# QuadEncoder.net
KiCad netlist of a schematic drawn in EAGLE
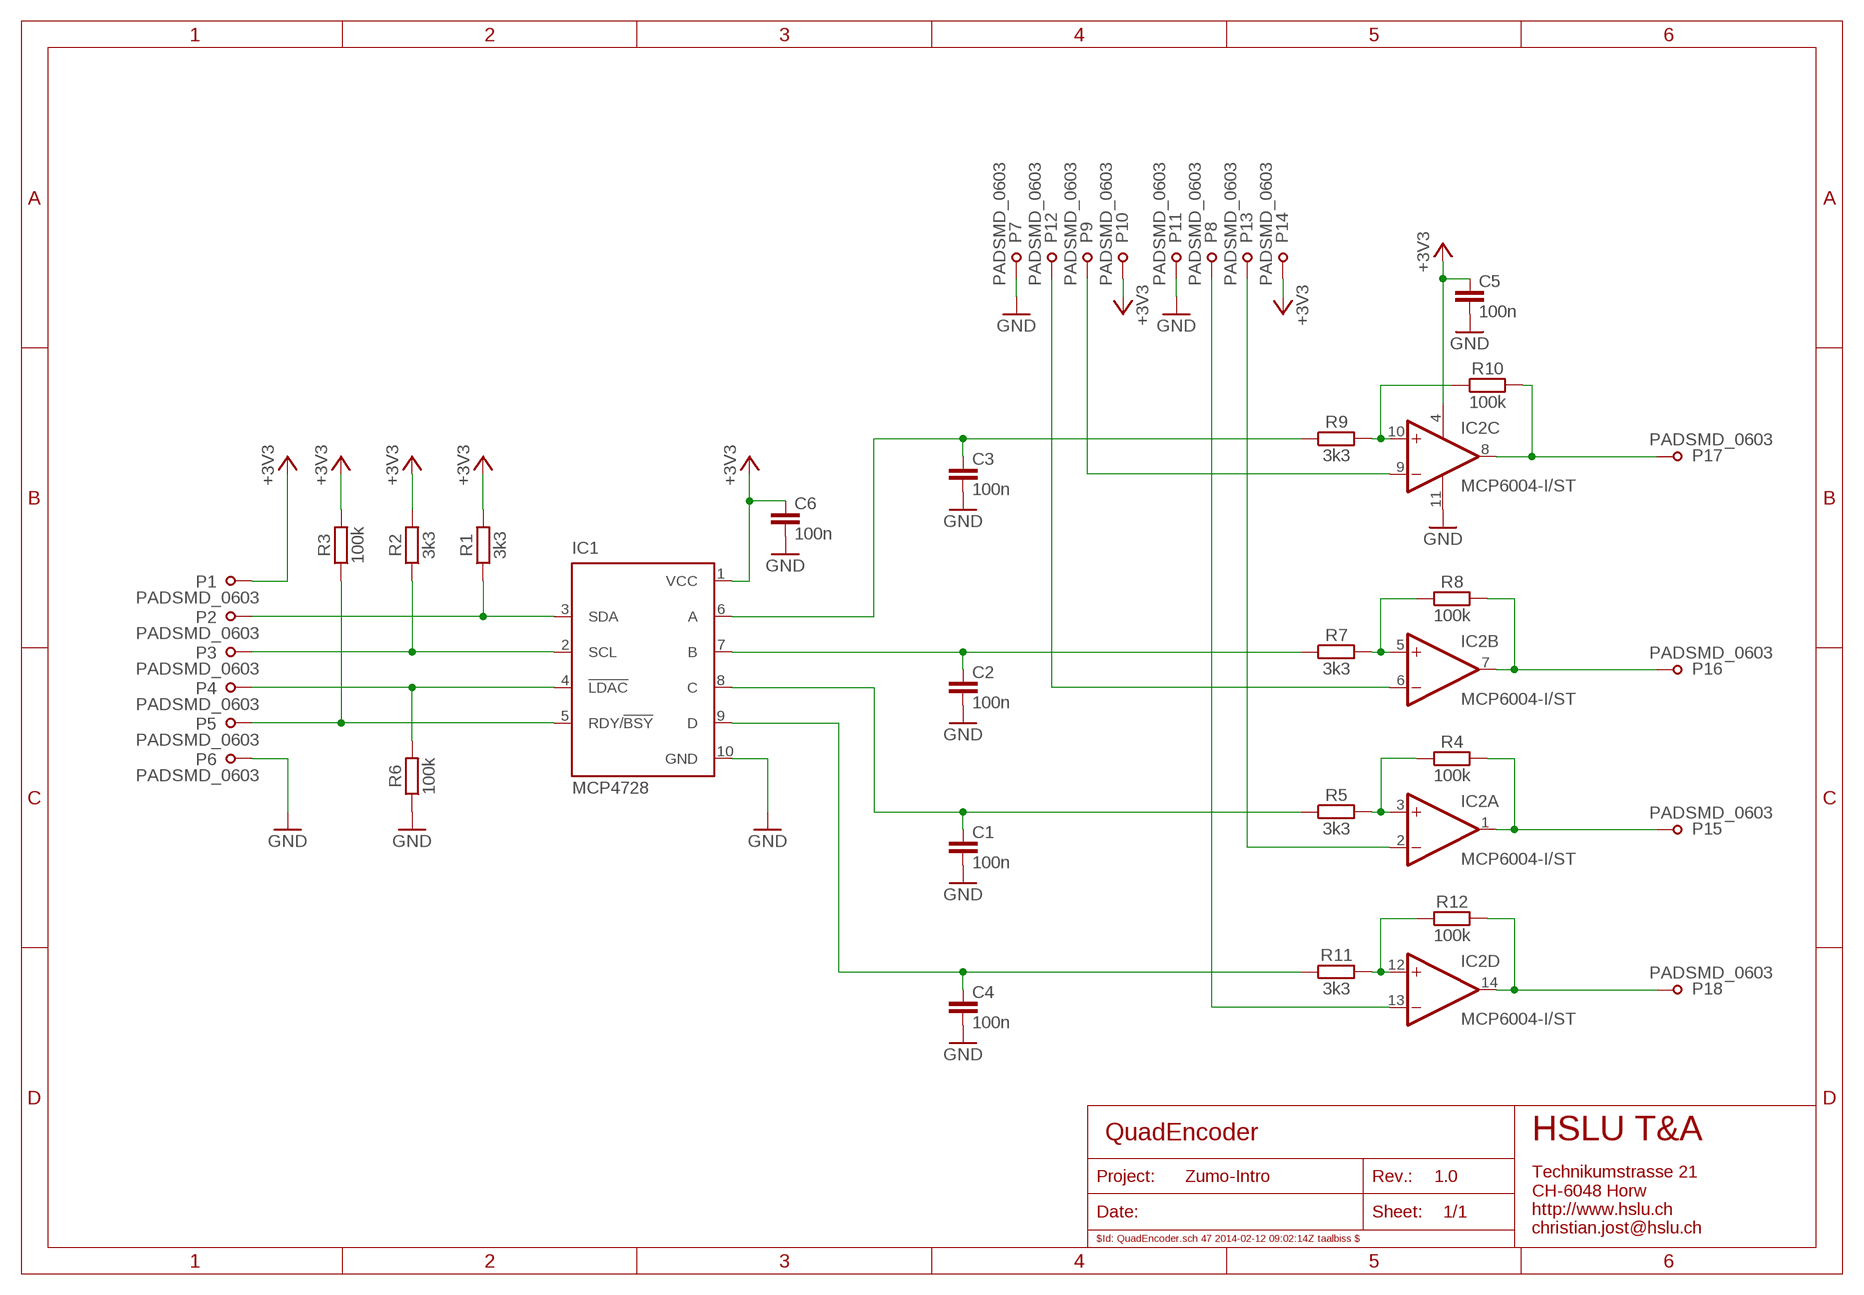
[diagram p0: schematic, sheet 1]

(export (version "E")
  (design (tool "Eeschema 10.0.6"))
  (components
    (comp (ref "C1")
      (value "100n")
      (footprint "eagle-import:C0805-R")
      (libsource (lib "eagle-import") (part "C0805"))
    )
    (comp (ref "C2")
      (value "100n")
      (footprint "eagle-import:C0805-R")
      (libsource (lib "eagle-import") (part "C0805"))
    )
    (comp (ref "C3")
      (value "100n")
      (footprint "eagle-import:C0805-R")
      (libsource (lib "eagle-import") (part "C0805"))
    )
    (comp (ref "C4")
      (value "100n")
      (footprint "eagle-import:C0805-R")
      (libsource (lib "eagle-import") (part "C0805"))
    )
    (comp (ref "C5")
      (value "100n")
      (footprint "eagle-import:C0805-R")
      (libsource (lib "eagle-import") (part "C0805"))
    )
    (comp (ref "C6")
      (value "100n")
      (footprint "eagle-import:C0805-R")
      (libsource (lib "eagle-import") (part "C0805"))
    )
    (comp (ref "IC1")
      (value "MCP4728")
      (footprint "eagle-import:MSOP10")
      (libsource (lib "eagle-import") (part "MCP4728"))
    )
    (comp (ref "IC2")
      (value "MCP6004-I/ST")
      (footprint "eagle-import:TSSOP14")
      (fields (field (name "DISTRIBUTOR") "Mouser") (field (name "DISTRIBUTOR_NR") "579-MCP6004-I/ST"))
      (libsource (lib "eagle-import") (part "MCP6004/ST-I"))
    )
    (comp (ref "P1")
      (value "PADSMD_0603")
      (footprint "eagle-import:PAD_SMD_0603")
      (libsource (lib "eagle-import") (part "PADSMD_0603"))
    )
    (comp (ref "P2")
      (value "PADSMD_0603")
      (footprint "eagle-import:PAD_SMD_0603")
      (libsource (lib "eagle-import") (part "PADSMD_0603"))
    )
    (comp (ref "P3")
      (value "PADSMD_0603")
      (footprint "eagle-import:PAD_SMD_0603")
      (libsource (lib "eagle-import") (part "PADSMD_0603"))
    )
    (comp (ref "P4")
      (value "PADSMD_0603")
      (footprint "eagle-import:PAD_SMD_0603")
      (libsource (lib "eagle-import") (part "PADSMD_0603"))
    )
    (comp (ref "P5")
      (value "PADSMD_0603")
      (footprint "eagle-import:PAD_SMD_0603")
      (libsource (lib "eagle-import") (part "PADSMD_0603"))
    )
    (comp (ref "P6")
      (value "PADSMD_0603")
      (footprint "eagle-import:PAD_SMD_0603")
      (libsource (lib "eagle-import") (part "PADSMD_0603"))
    )
    (comp (ref "P7")
      (value "PADSMD_0603")
      (footprint "eagle-import:PAD_SMD_0603")
      (libsource (lib "eagle-import") (part "PADSMD_0603"))
    )
    (comp (ref "P8")
      (value "PADSMD_0603")
      (footprint "eagle-import:PAD_SMD_0603")
      (libsource (lib "eagle-import") (part "PADSMD_0603"))
    )
    (comp (ref "P9")
      (value "PADSMD_0603")
      (footprint "eagle-import:PAD_SMD_0603")
      (libsource (lib "eagle-import") (part "PADSMD_0603"))
    )
    (comp (ref "P10")
      (value "PADSMD_0603")
      (footprint "eagle-import:PAD_SMD_0603")
      (libsource (lib "eagle-import") (part "PADSMD_0603"))
    )
    (comp (ref "P11")
      (value "PADSMD_0603")
      (footprint "eagle-import:PAD_SMD_0603")
      (libsource (lib "eagle-import") (part "PADSMD_0603"))
    )
    (comp (ref "P12")
      (value "PADSMD_0603")
      (footprint "eagle-import:PAD_SMD_0603")
      (libsource (lib "eagle-import") (part "PADSMD_0603"))
    )
    (comp (ref "P13")
      (value "PADSMD_0603")
      (footprint "eagle-import:PAD_SMD_0603")
      (libsource (lib "eagle-import") (part "PADSMD_0603"))
    )
    (comp (ref "P14")
      (value "PADSMD_0603")
      (footprint "eagle-import:PAD_SMD_0603")
      (libsource (lib "eagle-import") (part "PADSMD_0603"))
    )
    (comp (ref "P15")
      (value "PADSMD_0603")
      (footprint "eagle-import:PAD_SMD_0603")
      (libsource (lib "eagle-import") (part "PADSMD_0603"))
    )
    (comp (ref "P16")
      (value "PADSMD_0603")
      (footprint "eagle-import:PAD_SMD_0603")
      (libsource (lib "eagle-import") (part "PADSMD_0603"))
    )
    (comp (ref "P17")
      (value "PADSMD_0603")
      (footprint "eagle-import:PAD_SMD_0603")
      (libsource (lib "eagle-import") (part "PADSMD_0603"))
    )
    (comp (ref "P18")
      (value "PADSMD_0603")
      (footprint "eagle-import:PAD_SMD_0603")
      (libsource (lib "eagle-import") (part "PADSMD_0603"))
    )
    (comp (ref "R1")
      (value "3k3")
      (footprint "eagle-import:R0805-R")
      (libsource (lib "eagle-import") (part "R0805"))
    )
    (comp (ref "R2")
      (value "3k3")
      (footprint "eagle-import:R0805-R")
      (libsource (lib "eagle-import") (part "R0805"))
    )
    (comp (ref "R3")
      (value "100k")
      (footprint "eagle-import:R0805-R")
      (libsource (lib "eagle-import") (part "R0805"))
    )
    (comp (ref "R4")
      (value "100k")
      (footprint "eagle-import:R0805-R")
      (libsource (lib "eagle-import") (part "R0805"))
    )
    (comp (ref "R5")
      (value "3k3")
      (footprint "eagle-import:R0805-R")
      (libsource (lib "eagle-import") (part "R0805"))
    )
    (comp (ref "R6")
      (value "100k")
      (footprint "eagle-import:R0805-R")
      (libsource (lib "eagle-import") (part "R0805"))
    )
    (comp (ref "R7")
      (value "3k3")
      (footprint "eagle-import:R0805-R")
      (libsource (lib "eagle-import") (part "R0805"))
    )
    (comp (ref "R8")
      (value "100k")
      (footprint "eagle-import:R0805-R")
      (libsource (lib "eagle-import") (part "R0805"))
    )
    (comp (ref "R9")
      (value "3k3")
      (footprint "eagle-import:R0805-R")
      (libsource (lib "eagle-import") (part "R0805"))
    )
    (comp (ref "R10")
      (value "100k")
      (footprint "eagle-import:R0805-R")
      (libsource (lib "eagle-import") (part "R0805"))
    )
    (comp (ref "R11")
      (value "3k3")
      (footprint "eagle-import:R0805-R")
      (libsource (lib "eagle-import") (part "R0805"))
    )
    (comp (ref "R12")
      (value "100k")
      (footprint "eagle-import:R0805-R")
      (libsource (lib "eagle-import") (part "R0805"))
    )
  )
  (nets
    (net (code "1") (name "+3V3") (class "Default")
      (node (ref "C5") (pin "1") (pinfunction "1_1") (pintype "passive"))
      (node (ref "C6") (pin "1") (pinfunction "1_1") (pintype "passive"))
      (node (ref "IC1") (pin "1") (pinfunction "VCC_1") (pintype "power_in"))
      (node (ref "IC2") (pin "4") (pinfunction "V+_4") (pintype "power_in"))
      (node (ref "P1") (pin "1") (pinfunction "1_1") (pintype "passive"))
      (node (ref "P10") (pin "1") (pinfunction "1_1") (pintype "passive"))
      (node (ref "P14") (pin "1") (pinfunction "1_1") (pintype "passive"))
      (node (ref "R1") (pin "2") (pinfunction "2_2") (pintype "passive"))
      (node (ref "R2") (pin "2") (pinfunction "2_2") (pintype "passive"))
      (node (ref "R3") (pin "2") (pinfunction "2_2") (pintype "passive"))
    )
    (net (code "2") (name "GND") (class "Default")
      (node (ref "C1") (pin "2") (pinfunction "2_2") (pintype "passive"))
      (node (ref "C2") (pin "2") (pinfunction "2_2") (pintype "passive"))
      (node (ref "C3") (pin "2") (pinfunction "2_2") (pintype "passive"))
      (node (ref "C4") (pin "2") (pinfunction "2_2") (pintype "passive"))
      (node (ref "C5") (pin "2") (pinfunction "2_2") (pintype "passive"))
      (node (ref "C6") (pin "2") (pinfunction "2_2") (pintype "passive"))
      (node (ref "IC1") (pin "10") (pinfunction "GND_10") (pintype "power_in"))
      (node (ref "IC2") (pin "11") (pinfunction "V-_11") (pintype "power_in"))
      (node (ref "P11") (pin "1") (pinfunction "1_1") (pintype "passive"))
      (node (ref "P6") (pin "1") (pinfunction "1_1") (pintype "passive"))
      (node (ref "P7") (pin "1") (pinfunction "1_1") (pintype "passive"))
      (node (ref "R6") (pin "1") (pinfunction "1_1") (pintype "passive"))
    )
    (net (code "3") (name "Net-(IC1-A)") (class "Default")
      (node (ref "C3") (pin "1") (pinfunction "1_1") (pintype "passive"))
      (node (ref "IC1") (pin "6") (pinfunction "A_6") (pintype "bidirectional"))
      (node (ref "R9") (pin "1") (pinfunction "1_1") (pintype "passive"))
    )
    (net (code "4") (name "Net-(IC1-B)") (class "Default")
      (node (ref "C2") (pin "1") (pinfunction "1_1") (pintype "passive"))
      (node (ref "IC1") (pin "7") (pinfunction "B_7") (pintype "bidirectional"))
      (node (ref "R7") (pin "1") (pinfunction "1_1") (pintype "passive"))
    )
    (net (code "5") (name "Net-(IC1-C)") (class "Default")
      (node (ref "C1") (pin "1") (pinfunction "1_1") (pintype "passive"))
      (node (ref "IC1") (pin "8") (pinfunction "C_8") (pintype "bidirectional"))
      (node (ref "R5") (pin "1") (pinfunction "1_1") (pintype "passive"))
    )
    (net (code "6") (name "Net-(IC1-D)") (class "Default")
      (node (ref "C4") (pin "1") (pinfunction "1_1") (pintype "passive"))
      (node (ref "IC1") (pin "9") (pinfunction "D_9") (pintype "bidirectional"))
      (node (ref "R11") (pin "1") (pinfunction "1_1") (pintype "passive"))
    )
    (net (code "7") (name "Net-(IC1-RDY{slash}~{BSY})") (class "Default")
      (node (ref "IC1") (pin "5") (pinfunction "RDY/~{BSY}_5") (pintype "output"))
      (node (ref "P5") (pin "1") (pinfunction "1_1") (pintype "passive"))
      (node (ref "R3") (pin "1") (pinfunction "1_1") (pintype "passive"))
    )
    (net (code "8") (name "Net-(IC1-SCL)") (class "Default")
      (node (ref "IC1") (pin "2") (pinfunction "SCL_2") (pintype "output"))
      (node (ref "P3") (pin "1") (pinfunction "1_1") (pintype "passive"))
      (node (ref "R2") (pin "1") (pinfunction "1_1") (pintype "passive"))
    )
    (net (code "9") (name "Net-(IC1-SDA)") (class "Default")
      (node (ref "IC1") (pin "3") (pinfunction "SDA_3") (pintype "input"))
      (node (ref "P2") (pin "1") (pinfunction "1_1") (pintype "passive"))
      (node (ref "R1") (pin "1") (pinfunction "1_1") (pintype "passive"))
    )
    (net (code "10") (name "Net-(IC1-~{LDAC})") (class "Default")
      (node (ref "IC1") (pin "4") (pinfunction "~{LDAC}_4") (pintype "input"))
      (node (ref "P4") (pin "1") (pinfunction "1_1") (pintype "passive"))
      (node (ref "R6") (pin "2") (pinfunction "2_2") (pintype "passive"))
    )
    (net (code "11") (name "Net-(IC2A-IN+)") (class "Default")
      (node (ref "IC2") (pin "3") (pinfunction "IN+_3") (pintype "input"))
      (node (ref "R4") (pin "1") (pinfunction "1_1") (pintype "passive"))
      (node (ref "R5") (pin "2") (pinfunction "2_2") (pintype "passive"))
    )
    (net (code "12") (name "Net-(IC2A-IN-)") (class "Default")
      (node (ref "IC2") (pin "2") (pinfunction "IN-_2") (pintype "input"))
      (node (ref "P13") (pin "1") (pinfunction "1_1") (pintype "passive"))
    )
    (net (code "13") (name "Net-(IC2A-OUT)") (class "Default")
      (node (ref "IC2") (pin "1") (pinfunction "OUT_1") (pintype "output"))
      (node (ref "P15") (pin "1") (pinfunction "1_1") (pintype "passive"))
      (node (ref "R4") (pin "2") (pinfunction "2_2") (pintype "passive"))
    )
    (net (code "14") (name "Net-(IC2B-IN+)") (class "Default")
      (node (ref "IC2") (pin "5") (pinfunction "IN+_5") (pintype "input"))
      (node (ref "R7") (pin "2") (pinfunction "2_2") (pintype "passive"))
      (node (ref "R8") (pin "1") (pinfunction "1_1") (pintype "passive"))
    )
    (net (code "15") (name "Net-(IC2B-IN-)") (class "Default")
      (node (ref "IC2") (pin "6") (pinfunction "IN-_6") (pintype "input"))
      (node (ref "P12") (pin "1") (pinfunction "1_1") (pintype "passive"))
    )
    (net (code "16") (name "Net-(IC2B-OUT)") (class "Default")
      (node (ref "IC2") (pin "7") (pinfunction "OUT_7") (pintype "output"))
      (node (ref "P16") (pin "1") (pinfunction "1_1") (pintype "passive"))
      (node (ref "R8") (pin "2") (pinfunction "2_2") (pintype "passive"))
    )
    (net (code "17") (name "Net-(IC2C-IN+)") (class "Default")
      (node (ref "IC2") (pin "10") (pinfunction "IN+_10") (pintype "input"))
      (node (ref "R10") (pin "1") (pinfunction "1_1") (pintype "passive"))
      (node (ref "R9") (pin "2") (pinfunction "2_2") (pintype "passive"))
    )
    (net (code "18") (name "Net-(IC2C-IN-)") (class "Default")
      (node (ref "IC2") (pin "9") (pinfunction "IN-_9") (pintype "input"))
      (node (ref "P9") (pin "1") (pinfunction "1_1") (pintype "passive"))
    )
    (net (code "19") (name "Net-(IC2C-OUT)") (class "Default")
      (node (ref "IC2") (pin "8") (pinfunction "OUT_8") (pintype "output"))
      (node (ref "P17") (pin "1") (pinfunction "1_1") (pintype "passive"))
      (node (ref "R10") (pin "2") (pinfunction "2_2") (pintype "passive"))
    )
    (net (code "20") (name "Net-(IC2D-IN+)") (class "Default")
      (node (ref "IC2") (pin "12") (pinfunction "IN+_12") (pintype "input"))
      (node (ref "R11") (pin "2") (pinfunction "2_2") (pintype "passive"))
      (node (ref "R12") (pin "1") (pinfunction "1_1") (pintype "passive"))
    )
    (net (code "21") (name "Net-(IC2D-IN-)") (class "Default")
      (node (ref "IC2") (pin "13") (pinfunction "IN-_13") (pintype "input"))
      (node (ref "P8") (pin "1") (pinfunction "1_1") (pintype "passive"))
    )
    (net (code "22") (name "Net-(IC2D-OUT)") (class "Default")
      (node (ref "IC2") (pin "14") (pinfunction "OUT_14") (pintype "output"))
      (node (ref "P18") (pin "1") (pinfunction "1_1") (pintype "passive"))
      (node (ref "R12") (pin "2") (pinfunction "2_2") (pintype "passive"))
    )
  )
)
